# USB_POWER.net
KiCad netlist of a schematic drawn in Altium Designer
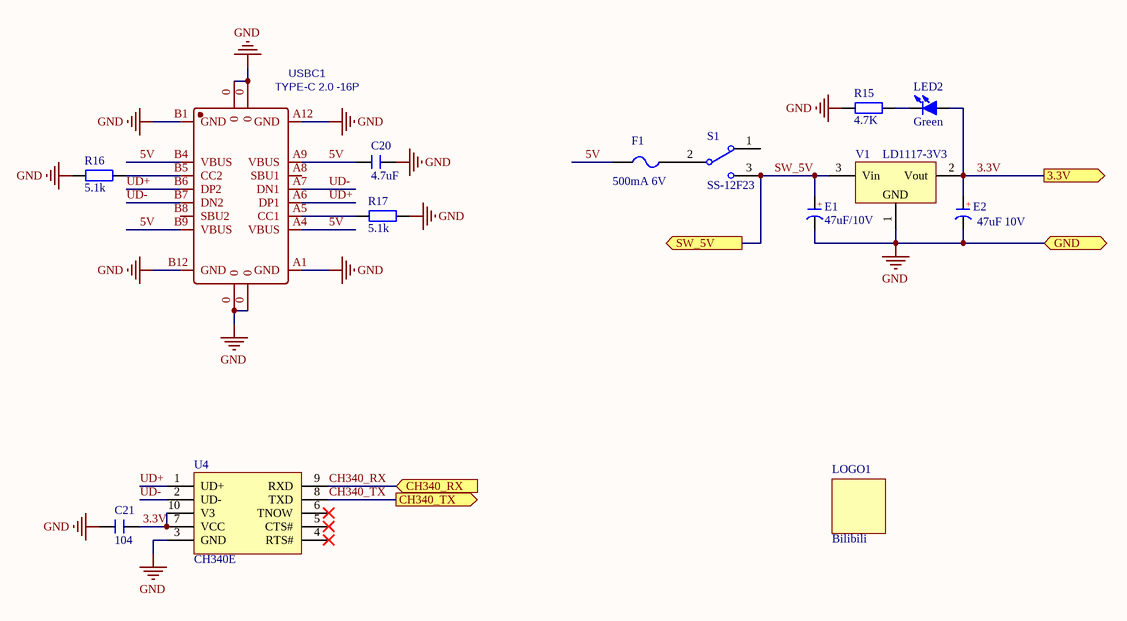
[diagram p0: USB_POWER.SchDoc]

(export (version "E")
  (design (tool "Eeschema 10.0.6"))
  (components
    (comp (ref "C20")
      (value "4.7uF")
      (footprint "C 0603_L")
      (description "贴片电容")
      (libsource (lib "0.1 - 电阻-电容-电感") (part "C"))
    )
    (comp (ref "C21")
      (value "104")
      (footprint "C 0603_L")
      (description "贴片电容")
      (libsource (lib "0.1 - 电阻-电容-电感") (part "C"))
    )
    (comp (ref "E1")
      (value "47uF/10V")
      (footprint "CM B(4*5.4)")
      (description "贴片电解电容")
      (libsource (lib "0.1 - 电阻-电容-电感") (part "CE_SMD"))
    )
    (comp (ref "E2")
      (value "47uF 10V")
      (footprint "CM B(4*5.4)")
      (description "贴片电解电容")
      (libsource (lib "0.1 - 电阻-电容-电感") (part "CE_SMD"))
    )
    (comp (ref "F1")
      (value "500mA 6V")
      (footprint "R 0603-HP_L")
      (description "贴片保险丝")
      (fields (field (name "版权归属") "封装库来自淘宝卖家 ID：黄晶宝石"))
      (libsource (lib "0.5 - 保险丝-晶振-光耦") (part "FU"))
    )
    (comp (ref "LED2")
      (value "Green")
      (footprint "LED_0603")
      (description "贴片LED")
      (libsource (lib "0.3 - LED发光二极管") (part "LED-SMD"))
    )
    (comp (ref "LOGO1")
      (value "Bilibili")
      (footprint "Bilibili")
      (description "LOGO")
      (libsource (lib "LOGO") (part "LOGO"))
    )
    (comp (ref "R15")
      (value "4.7K")
      (footprint "R 0603_L")
      (description "贴片电阻")
      (libsource (lib "0.1 - 电阻-电容-电感") (part "R"))
    )
    (comp (ref "R16")
      (value "5.1k")
      (footprint "R 0603_L")
      (description "贴片电阻")
      (libsource (lib "0.1 - 电阻-电容-电感") (part "R"))
    )
    (comp (ref "R17")
      (value "5.1k")
      (footprint "R 0603_L")
      (description "贴片电阻")
      (libsource (lib "0.1 - 电阻-电容-电感") (part "R"))
    )
    (comp (ref "S1")
      (value "SS-12F23")
      (footprint "MSK-12C01-07")
      (description "1路波动开关")
      (fields (field (name "版权归属") "封装库来自淘宝 ID：黄晶宝石"))
      (libsource (lib "0.7 - 常用按键-开关-蜂鸣器-电池") (part "SSW-1P"))
    )
    (comp (ref "U4")
      (value "CH340E")
      (footprint "MSOP10_L")
      (libsource (lib "1.9 - CH340系列编程器芯片") (part "CH340E"))
    )
    (comp (ref "USBC1")
      (value "TYPE-C 2.0 -16P")
      (footprint "USB-C-SMD_TYPE-C-USB-5")
      (description "USB2.0 Type-C 母座 16Pin")
      (libsource (lib "0.8 - 以太网-音频-USB插座") (part "USB2.0 Type-C 16Pin母座"))
    )
    (comp (ref "V1")
      (value "LD1117-3V3")
      (footprint "SOT223_L")
      (description "三端稳压芯片")
      (libsource (lib "1.1 - 电源类芯片") (part "LD1117"))
    )
  )
  (nets
    (net (code "1") (name "/3.3V") (class "Default")
      (node (ref "C21") (pin "1") (pinfunction "1_1") (pintype "passive"))
      (node (ref "E2") (pin "1") (pinfunction "A_1") (pintype "passive"))
      (node (ref "LED2") (pin "1") (pinfunction "A_1") (pintype "passive"))
      (node (ref "U4") (pin "10") (pinfunction "V3_10") (pintype "passive"))
      (node (ref "U4") (pin "7") (pinfunction "VCC_7") (pintype "passive"))
      (node (ref "V1") (pin "2") (pinfunction "Vout_2") (pintype "passive"))
    )
    (net (code "2") (name "/5V") (class "Default")
      (node (ref "C20") (pin "1") (pinfunction "1_1") (pintype "passive"))
      (node (ref "F1") (pin "1") (pinfunction "1_1") (pintype "passive"))
      (node (ref "USBC1") (pin "A4") (pinfunction "VBUS_A4") (pintype "passive"))
      (node (ref "USBC1") (pin "A9") (pinfunction "VBUS_A9") (pintype "passive"))
      (node (ref "USBC1") (pin "B4") (pinfunction "VBUS_B4") (pintype "passive"))
      (node (ref "USBC1") (pin "B9") (pinfunction "VBUS_B9") (pintype "passive"))
    )
    (net (code "3") (name "/CH340_RX") (class "Default")
      (node (ref "U4") (pin "9") (pinfunction "RXD_9") (pintype "passive"))
    )
    (net (code "4") (name "/CH340_TX") (class "Default")
      (node (ref "U4") (pin "8") (pinfunction "TXD_8") (pintype "passive"))
    )
    (net (code "5") (name "/SW_5V") (class "Default")
      (node (ref "E1") (pin "1") (pinfunction "A_1") (pintype "passive"))
      (node (ref "S1") (pin "3") (pinfunction "3_3") (pintype "passive"))
      (node (ref "V1") (pin "3") (pinfunction "Vin_3") (pintype "passive"))
    )
    (net (code "6") (name "/UD+") (class "Default")
      (node (ref "U4") (pin "1") (pinfunction "UD+_1") (pintype "passive"))
      (node (ref "USBC1") (pin "A6") (pinfunction "DP1_A6") (pintype "passive"))
      (node (ref "USBC1") (pin "B6") (pinfunction "DP2_B6") (pintype "passive"))
    )
    (net (code "7") (name "/UD-") (class "Default")
      (node (ref "U4") (pin "2") (pinfunction "UD-_2") (pintype "passive"))
      (node (ref "USBC1") (pin "A7") (pinfunction "DN1_A7") (pintype "passive"))
      (node (ref "USBC1") (pin "B7") (pinfunction "DN2_B7") (pintype "passive"))
    )
    (net (code "8") (name "GND") (class "Default")
      (node (ref "C20") (pin "2") (pinfunction "2_2") (pintype "passive"))
      (node (ref "C21") (pin "2") (pinfunction "2_2") (pintype "passive"))
      (node (ref "E1") (pin "2") (pinfunction "K_2") (pintype "passive"))
      (node (ref "E2") (pin "2") (pinfunction "K_2") (pintype "passive"))
      (node (ref "R15") (pin "2") (pinfunction "2_2") (pintype "passive"))
      (node (ref "R16") (pin "2") (pinfunction "2_2") (pintype "passive"))
      (node (ref "R17") (pin "1") (pinfunction "1_1") (pintype "passive"))
      (node (ref "U4") (pin "3") (pinfunction "GND_3") (pintype "passive"))
      (node (ref "USBC1") (pin "0") (pinfunction "0_0") (pintype "passive"))
      (node (ref "USBC1") (pin "A1") (pinfunction "GND_A1") (pintype "passive"))
      (node (ref "USBC1") (pin "A12") (pinfunction "GND_A12") (pintype "passive"))
      (node (ref "USBC1") (pin "B1") (pinfunction "GND_B1") (pintype "passive"))
      (node (ref "USBC1") (pin "B12") (pinfunction "GND_B12") (pintype "passive"))
      (node (ref "V1") (pin "1") (pinfunction "GND_1") (pintype "passive"))
    )
    (net (code "9") (name "Net-(F1-Pad2)") (class "Default")
      (node (ref "F1") (pin "2") (pinfunction "2_2") (pintype "passive"))
      (node (ref "S1") (pin "2") (pinfunction "2_2") (pintype "passive"))
    )
    (net (code "10") (name "Net-(LED2-K)") (class "Default")
      (node (ref "LED2") (pin "2") (pinfunction "K_2") (pintype "passive"))
      (node (ref "R15") (pin "1") (pinfunction "1_1") (pintype "passive"))
    )
    (net (code "11") (name "Net-(USBC1-CC1)") (class "Default")
      (node (ref "R17") (pin "2") (pinfunction "2_2") (pintype "passive"))
      (node (ref "USBC1") (pin "A5") (pinfunction "CC1_A5") (pintype "passive"))
    )
    (net (code "12") (name "Net-(USBC1-CC2)") (class "Default")
      (node (ref "R16") (pin "1") (pinfunction "1_1") (pintype "passive"))
      (node (ref "USBC1") (pin "B5") (pinfunction "CC2_B5") (pintype "passive"))
    )
    (net (code "13") (name "unconnected-(S1-Pad1)") (class "Default")
      (node (ref "S1") (pin "1") (pinfunction "1_1") (pintype "passive"))
    )
    (net (code "14") (name "unconnected-(U4-CTS#-Pad5)") (class "Default")
      (node (ref "U4") (pin "5") (pinfunction "CTS#_5") (pintype "passive+no_connect"))
    )
    (net (code "15") (name "unconnected-(U4-RTS#-Pad4)") (class "Default")
      (node (ref "U4") (pin "4") (pinfunction "RTS#_4") (pintype "passive+no_connect"))
    )
    (net (code "16") (name "unconnected-(U4-TNOW-Pad6)") (class "Default")
      (node (ref "U4") (pin "6") (pinfunction "TNOW_6") (pintype "passive+no_connect"))
    )
    (net (code "17") (name "unconnected-(USBC1-SBU1-PadA8)") (class "Default")
      (node (ref "USBC1") (pin "A8") (pinfunction "SBU1_A8") (pintype "passive"))
    )
    (net (code "18") (name "unconnected-(USBC1-SBU2-PadB8)") (class "Default")
      (node (ref "USBC1") (pin "B8") (pinfunction "SBU2_B8") (pintype "passive"))
    )
  )
)
